# bristol_longshot.net
KiCad netlist of a schematic drawn in EAGLE
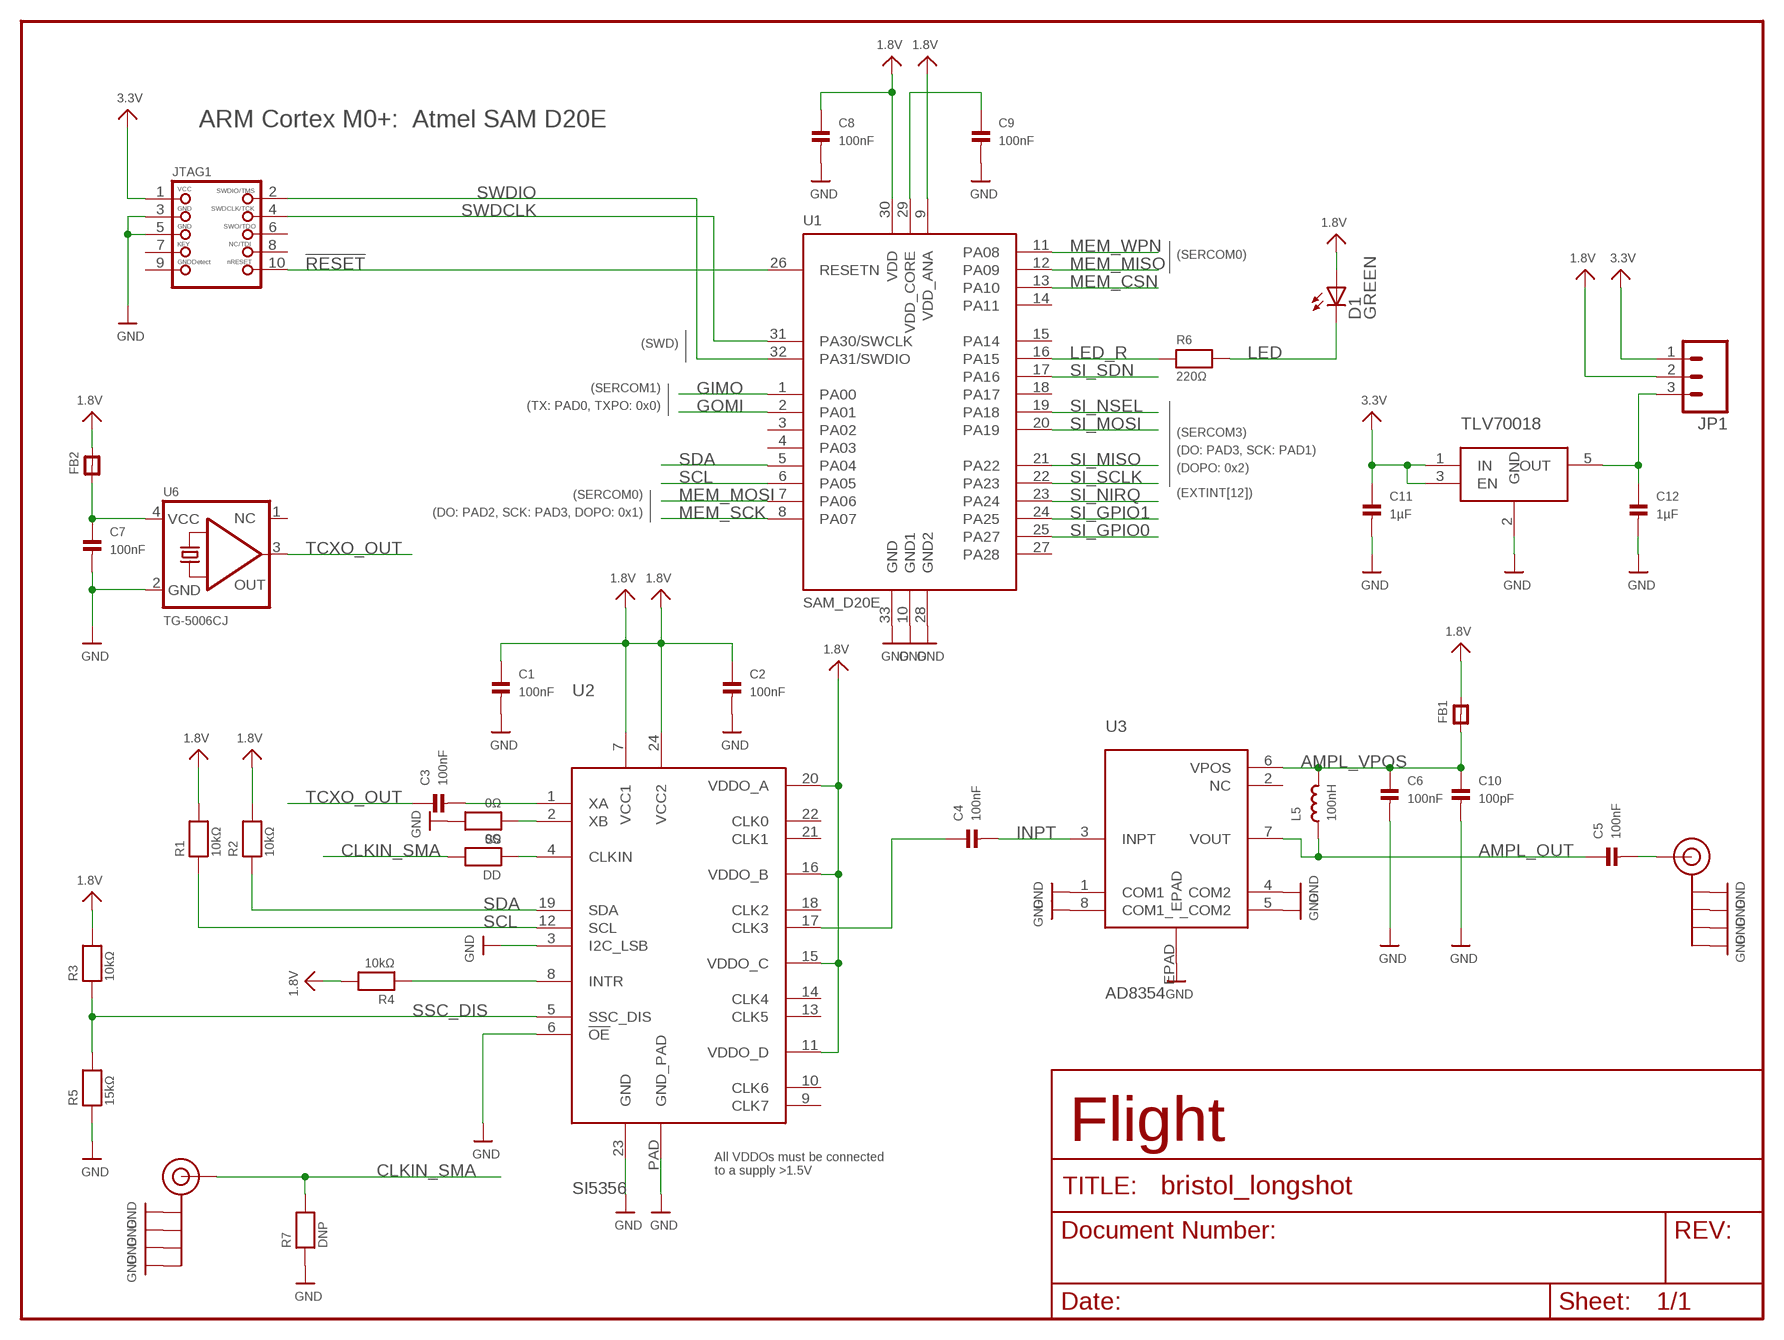
[diagram p0: schematic, sheet 1]

(export (version "E")
  (design (tool "Eeschema 10.0.6"))
  (components
    (comp (ref "C1")
      (value "100nF")
      (footprint "eagle-import:_0402")
      (libsource (lib "eagle-import") (part "CAP_CERAMIC_0402"))
    )
    (comp (ref "C2")
      (value "100nF")
      (footprint "eagle-import:_0402")
      (libsource (lib "eagle-import") (part "CAP_CERAMIC_0402"))
    )
    (comp (ref "C3")
      (value "100nF")
      (footprint "eagle-import:_0402")
      (libsource (lib "eagle-import") (part "CAP_CERAMIC_0402"))
    )
    (comp (ref "C4")
      (value "100nF")
      (footprint "eagle-import:_0402")
      (libsource (lib "eagle-import") (part "CAP_CERAMIC_0402"))
    )
    (comp (ref "C5")
      (value "100nF")
      (footprint "eagle-import:_0402")
      (libsource (lib "eagle-import") (part "CAP_CERAMIC_0402"))
    )
    (comp (ref "C6")
      (value "100nF")
      (footprint "eagle-import:_0402")
      (libsource (lib "eagle-import") (part "CAP_CERAMIC_0402"))
    )
    (comp (ref "C7")
      (value "100nF")
      (footprint "eagle-import:_0402")
      (libsource (lib "eagle-import") (part "CAP_CERAMIC_0402"))
    )
    (comp (ref "C8")
      (value "100nF")
      (footprint "eagle-import:_0402")
      (libsource (lib "eagle-import") (part "CAP_CERAMIC_0402"))
    )
    (comp (ref "C9")
      (value "100nF")
      (footprint "eagle-import:_0402")
      (libsource (lib "eagle-import") (part "CAP_CERAMIC_0402"))
    )
    (comp (ref "C10")
      (value "100pF")
      (footprint "eagle-import:_0402")
      (libsource (lib "eagle-import") (part "CAP_CERAMIC_0402"))
    )
    (comp (ref "C11")
      (value "1µF")
      (footprint "eagle-import:_0402")
      (libsource (lib "eagle-import") (part "CAP_CERAMIC_0402"))
    )
    (comp (ref "C12")
      (value "1µF")
      (footprint "eagle-import:_0402")
      (libsource (lib "eagle-import") (part "CAP_CERAMIC_0402"))
    )
    (comp (ref "D1")
      (value "GREEN")
      (footprint "eagle-import:CHIPLED_0603")
      (libsource (lib "eagle-import") (part "LEDCHIPLED_0603"))
    )
    (comp (ref "DD")
      (value "0Ω")
      (footprint "eagle-import:_0402")
      (libsource (lib "eagle-import") (part "RESISTOR_0402"))
    )
    (comp (ref "FB1")
      (value "FERRITE_0402")
      (footprint "eagle-import:_0402")
      (libsource (lib "eagle-import") (part "FERRITE_0402"))
    )
    (comp (ref "FB2")
      (value "FERRITE_0402")
      (footprint "eagle-import:_0402")
      (libsource (lib "eagle-import") (part "FERRITE_0402"))
    )
    (comp (ref "J$1")
      (value "SMA_EDGE")
      (footprint "eagle-import:SMA-EDGE")
      (libsource (lib "eagle-import") (part "SMA_EDGE"))
    )
    (comp (ref "J$2")
      (value "SMA_EDGE")
      (footprint "eagle-import:SMA-EDGE")
      (libsource (lib "eagle-import") (part "SMA_EDGE"))
    )
    (comp (ref "JP1")
      (value "M03LOCK")
      (footprint "eagle-import:1X03_LOCK")
      (libsource (lib "eagle-import") (part "M03LOCK"))
    )
    (comp (ref "JTAG1")
      (value "JTAG-CORTEXM3SMT")
      (footprint "eagle-import:2X05_1.27MM_SMT")
      (libsource (lib "eagle-import") (part "JTAG-CORTEXM3SMT"))
    )
    (comp (ref "L5")
      (value "100nH")
      (footprint "eagle-import:_0402")
      (libsource (lib "eagle-import") (part "INDUCTOR_0402"))
    )
    (comp (ref "R1")
      (value "10kΩ")
      (footprint "eagle-import:_0402")
      (libsource (lib "eagle-import") (part "RESISTOR_0402"))
    )
    (comp (ref "R2")
      (value "10kΩ")
      (footprint "eagle-import:_0402")
      (libsource (lib "eagle-import") (part "RESISTOR_0402"))
    )
    (comp (ref "R3")
      (value "10kΩ")
      (footprint "eagle-import:_0402")
      (libsource (lib "eagle-import") (part "RESISTOR_0402"))
    )
    (comp (ref "R4")
      (value "10kΩ")
      (footprint "eagle-import:_0402")
      (libsource (lib "eagle-import") (part "RESISTOR_0402"))
    )
    (comp (ref "R5")
      (value "15kΩ")
      (footprint "eagle-import:_0402")
      (libsource (lib "eagle-import") (part "RESISTOR_0402"))
    )
    (comp (ref "R6")
      (value "220Ω")
      (footprint "eagle-import:_0402")
      (libsource (lib "eagle-import") (part "RESISTOR_0402"))
    )
    (comp (ref "R7")
      (value "DNP")
      (footprint "eagle-import:_0402")
      (libsource (lib "eagle-import") (part "RESISTOR_0402"))
    )
    (comp (ref "SS")
      (value "0Ω")
      (footprint "eagle-import:_0402")
      (libsource (lib "eagle-import") (part "RESISTOR_0402"))
    )
    (comp (ref "U1")
      (value "SAM_D20E")
      (footprint "eagle-import:QFN32_5MM")
      (libsource (lib "eagle-import") (part "SAM_D20E"))
    )
    (comp (ref "U2")
      (value "SI5356")
      (footprint "eagle-import:QFN24_4MM")
      (libsource (lib "eagle-import") (part "SI5356"))
    )
    (comp (ref "U3")
      (value "AD8354")
      (footprint "eagle-import:LFCSP_VD_8")
      (libsource (lib "eagle-import") (part "AD8354"))
    )
    (comp (ref "U4")
      (value "TLV70018DCK")
      (footprint "eagle-import:SC70-5L")
      (libsource (lib "eagle-import") (part "TLV700DCK"))
    )
    (comp (ref "U6")
      (value "TG-5006CJ")
      (footprint "eagle-import:TC-5006CJ")
      (libsource (lib "eagle-import") (part "TG-5006CJ"))
    )
  )
  (nets
    (net (code "1") (name "/AMPL_OUT") (class "Default")
      (node (ref "C5") (pin "1") (pinfunction "P$1_1") (pintype "passive"))
      (node (ref "L5") (pin "1") (pinfunction "1_1") (pintype "passive"))
      (node (ref "U3") (pin "7") (pinfunction "VOUT_7") (pintype "bidirectional"))
    )
    (net (code "2") (name "/AMPL_VPOS") (class "Default")
      (node (ref "C10") (pin "1") (pinfunction "P$1_1") (pintype "passive"))
      (node (ref "C6") (pin "1") (pinfunction "P$1_1") (pintype "passive"))
      (node (ref "FB1") (pin "1") (pinfunction "P$1_1") (pintype "passive"))
      (node (ref "L5") (pin "2") (pinfunction "2_2") (pintype "passive"))
      (node (ref "U3") (pin "6") (pinfunction "VPOS_6") (pintype "bidirectional"))
    )
    (net (code "3") (name "/CLKIN_SMA") (class "Default")
      (node (ref "DD") (pin "2") (pinfunction "2_2") (pintype "passive"))
      (node (ref "J$1") (pin "SIG") (pinfunction "SIGNAL_SIG") (pintype "bidirectional"))
      (node (ref "R7") (pin "2") (pinfunction "2_2") (pintype "passive"))
    )
    (net (code "4") (name "/GIMO") (class "Default")
      (node (ref "U1") (pin "1") (pinfunction "PA00_1") (pintype "bidirectional"))
    )
    (net (code "5") (name "/GOMI") (class "Default")
      (node (ref "U1") (pin "2") (pinfunction "PA01_2") (pintype "bidirectional"))
    )
    (net (code "6") (name "/INPT") (class "Default")
      (node (ref "C4") (pin "2") (pinfunction "P$2_2") (pintype "passive"))
      (node (ref "U3") (pin "3") (pinfunction "INPT_3") (pintype "bidirectional"))
    )
    (net (code "7") (name "/LED") (class "Default")
      (node (ref "D1") (pin "C") (pinfunction "C_C") (pintype "passive"))
      (node (ref "R6") (pin "2") (pinfunction "2_2") (pintype "passive"))
    )
    (net (code "8") (name "/LED_R") (class "Default")
      (node (ref "R6") (pin "1") (pinfunction "1_1") (pintype "passive"))
      (node (ref "U1") (pin "16") (pinfunction "PA15_16") (pintype "bidirectional"))
    )
    (net (code "9") (name "/MEM_CSN") (class "Default")
      (node (ref "U1") (pin "13") (pinfunction "PA10_13") (pintype "bidirectional"))
    )
    (net (code "10") (name "/MEM_MISO") (class "Default")
      (node (ref "U1") (pin "12") (pinfunction "PA09_12") (pintype "bidirectional"))
    )
    (net (code "11") (name "/MEM_MOSI") (class "Default")
      (node (ref "U1") (pin "7") (pinfunction "PA06_7") (pintype "bidirectional"))
    )
    (net (code "12") (name "/MEM_SCK") (class "Default")
      (node (ref "U1") (pin "8") (pinfunction "PA07_8") (pintype "bidirectional"))
    )
    (net (code "13") (name "/MEM_WPN") (class "Default")
      (node (ref "U1") (pin "11") (pinfunction "PA08_11") (pintype "bidirectional"))
    )
    (net (code "14") (name "/SCL") (class "Default")
      (node (ref "R1") (pin "1") (pinfunction "1_1") (pintype "passive"))
      (node (ref "U1") (pin "6") (pinfunction "PA05_6") (pintype "bidirectional"))
      (node (ref "U2") (pin "12") (pinfunction "SCL_12") (pintype "bidirectional"))
    )
    (net (code "15") (name "/SDA") (class "Default")
      (node (ref "R2") (pin "1") (pinfunction "1_1") (pintype "passive"))
      (node (ref "U1") (pin "5") (pinfunction "PA04_5") (pintype "bidirectional"))
      (node (ref "U2") (pin "19") (pinfunction "SDA_19") (pintype "bidirectional"))
    )
    (net (code "16") (name "/SI_GPIO0") (class "Default")
      (node (ref "U1") (pin "25") (pinfunction "PA27_25") (pintype "bidirectional"))
    )
    (net (code "17") (name "/SI_GPIO1") (class "Default")
      (node (ref "U1") (pin "24") (pinfunction "PA25_24") (pintype "bidirectional"))
    )
    (net (code "18") (name "/SI_MISO") (class "Default")
      (node (ref "U1") (pin "21") (pinfunction "PA22_21") (pintype "bidirectional"))
    )
    (net (code "19") (name "/SI_MOSI") (class "Default")
      (node (ref "U1") (pin "20") (pinfunction "PA19_20") (pintype "bidirectional"))
    )
    (net (code "20") (name "/SI_NIRQ") (class "Default")
      (node (ref "U1") (pin "23") (pinfunction "PA24_23") (pintype "bidirectional"))
    )
    (net (code "21") (name "/SI_NSEL") (class "Default")
      (node (ref "U1") (pin "19") (pinfunction "PA18_19") (pintype "bidirectional"))
    )
    (net (code "22") (name "/SI_SCLK") (class "Default")
      (node (ref "U1") (pin "22") (pinfunction "PA23_22") (pintype "bidirectional"))
    )
    (net (code "23") (name "/SI_SDN") (class "Default")
      (node (ref "U1") (pin "17") (pinfunction "PA16_17") (pintype "bidirectional"))
    )
    (net (code "24") (name "/SSC_DIS") (class "Default")
      (node (ref "R3") (pin "1") (pinfunction "1_1") (pintype "passive"))
      (node (ref "R5") (pin "2") (pinfunction "2_2") (pintype "passive"))
      (node (ref "U2") (pin "5") (pinfunction "SSC_DIS_5") (pintype "bidirectional"))
    )
    (net (code "25") (name "/SWDCLK") (class "Default")
      (node (ref "JTAG1") (pin "4") (pinfunction "4_4") (pintype "passive"))
      (node (ref "U1") (pin "31") (pinfunction "PA30/SWCLK_31") (pintype "bidirectional"))
    )
    (net (code "26") (name "/SWDIO") (class "Default")
      (node (ref "JTAG1") (pin "2") (pinfunction "2_2") (pintype "passive"))
      (node (ref "U1") (pin "32") (pinfunction "PA31/SWDIO_32") (pintype "bidirectional"))
    )
    (net (code "27") (name "/TCXO_OUT") (class "Default")
      (node (ref "C3") (pin "1") (pinfunction "P$1_1") (pintype "passive"))
      (node (ref "U6") (pin "3") (pinfunction "OUT_3") (pintype "output"))
    )
    (net (code "28") (name "/~{RESET}") (class "Default")
      (node (ref "JTAG1") (pin "10") (pinfunction "10_10") (pintype "passive"))
      (node (ref "U1") (pin "26") (pinfunction "RESETN_26") (pintype "input"))
    )
    (net (code "29") (name "1.8V") (class "Default")
      (node (ref "C1") (pin "1") (pinfunction "P$1_1") (pintype "passive"))
      (node (ref "C2") (pin "1") (pinfunction "P$1_1") (pintype "passive"))
      (node (ref "C8") (pin "1") (pinfunction "P$1_1") (pintype "passive"))
      (node (ref "D1") (pin "A") (pinfunction "A_A") (pintype "passive"))
      (node (ref "FB1") (pin "2") (pinfunction "P$2_2") (pintype "passive"))
      (node (ref "FB2") (pin "2") (pinfunction "P$2_2") (pintype "passive"))
      (node (ref "JP1") (pin "2") (pinfunction "2_2") (pintype "passive"))
      (node (ref "R1") (pin "2") (pinfunction "2_2") (pintype "passive"))
      (node (ref "R2") (pin "2") (pinfunction "2_2") (pintype "passive"))
      (node (ref "R3") (pin "2") (pinfunction "2_2") (pintype "passive"))
      (node (ref "R4") (pin "2") (pinfunction "2_2") (pintype "passive"))
      (node (ref "U1") (pin "30") (pinfunction "VDD_30") (pintype "power_in"))
      (node (ref "U1") (pin "9") (pinfunction "VDD_ANA_9") (pintype "power_in"))
      (node (ref "U2") (pin "11") (pinfunction "VDDO_D_11") (pintype "bidirectional"))
      (node (ref "U2") (pin "15") (pinfunction "VDDO_C_15") (pintype "bidirectional"))
      (node (ref "U2") (pin "16") (pinfunction "VDDO_B_16") (pintype "bidirectional"))
      (node (ref "U2") (pin "20") (pinfunction "VDDO_A_20") (pintype "bidirectional"))
      (node (ref "U2") (pin "24") (pinfunction "VCC2_24") (pintype "bidirectional"))
      (node (ref "U2") (pin "7") (pinfunction "VCC1_7") (pintype "bidirectional"))
    )
    (net (code "30") (name "3.3V") (class "Default")
      (node (ref "C11") (pin "1") (pinfunction "P$1_1") (pintype "passive"))
      (node (ref "JP1") (pin "1") (pinfunction "1_1") (pintype "passive"))
      (node (ref "JTAG1") (pin "1") (pinfunction "1_1") (pintype "passive"))
      (node (ref "U4") (pin "1") (pinfunction "IN_1") (pintype "bidirectional"))
      (node (ref "U4") (pin "3") (pinfunction "EN_3") (pintype "bidirectional"))
    )
    (net (code "31") (name "GND") (class "Default")
      (node (ref "C1") (pin "2") (pinfunction "P$2_2") (pintype "passive"))
      (node (ref "C10") (pin "2") (pinfunction "P$2_2") (pintype "passive"))
      (node (ref "C11") (pin "2") (pinfunction "P$2_2") (pintype "passive"))
      (node (ref "C12") (pin "2") (pinfunction "P$2_2") (pintype "passive"))
      (node (ref "C2") (pin "2") (pinfunction "P$2_2") (pintype "passive"))
      (node (ref "C6") (pin "2") (pinfunction "P$2_2") (pintype "passive"))
      (node (ref "C7") (pin "2") (pinfunction "P$2_2") (pintype "passive"))
      (node (ref "C8") (pin "2") (pinfunction "P$2_2") (pintype "passive"))
      (node (ref "C9") (pin "2") (pinfunction "P$2_2") (pintype "passive"))
      (node (ref "J$1") (pin "GND@0") (pinfunction "GND_GND@0") (pintype "bidirectional"))
      (node (ref "J$1") (pin "GND@1") (pinfunction "GND_GND@1") (pintype "bidirectional"))
      (node (ref "J$1") (pin "GND@2") (pinfunction "GND_GND@2") (pintype "bidirectional"))
      (node (ref "J$1") (pin "GND@3") (pinfunction "GND_GND@3") (pintype "bidirectional"))
      (node (ref "J$2") (pin "GND@0") (pinfunction "GND_GND@0") (pintype "bidirectional"))
      (node (ref "J$2") (pin "GND@1") (pinfunction "GND_GND@1") (pintype "bidirectional"))
      (node (ref "J$2") (pin "GND@2") (pinfunction "GND_GND@2") (pintype "bidirectional"))
      (node (ref "J$2") (pin "GND@3") (pinfunction "GND_GND@3") (pintype "bidirectional"))
      (node (ref "JTAG1") (pin "3") (pinfunction "3_3") (pintype "passive"))
      (node (ref "JTAG1") (pin "5") (pinfunction "5_5") (pintype "passive"))
      (node (ref "R5") (pin "1") (pinfunction "1_1") (pintype "passive"))
      (node (ref "R7") (pin "1") (pinfunction "1_1") (pintype "passive"))
      (node (ref "SS") (pin "2") (pinfunction "2_2") (pintype "passive"))
      (node (ref "U1") (pin "10") (pinfunction "GND1_10") (pintype "power_in"))
      (node (ref "U1") (pin "28") (pinfunction "GND2_28") (pintype "power_in"))
      (node (ref "U1") (pin "33") (pinfunction "GND_33") (pintype "power_in"))
      (node (ref "U2") (pin "23") (pinfunction "GND_23") (pintype "bidirectional"))
      (node (ref "U2") (pin "3") (pinfunction "I2C_LSB_3") (pintype "bidirectional"))
      (node (ref "U2") (pin "6") (pinfunction "~{OE}_6") (pintype "bidirectional"))
      (node (ref "U2") (pin "PAD") (pinfunction "GND_PAD_PAD") (pintype "bidirectional"))
      (node (ref "U3") (pin "1") (pinfunction "COM1_1") (pintype "bidirectional"))
      (node (ref "U3") (pin "4") (pinfunction "COM2_4") (pintype "bidirectional"))
      (node (ref "U3") (pin "5") (pinfunction "_COM2_5") (pintype "bidirectional"))
      (node (ref "U3") (pin "8") (pinfunction "COM1__8") (pintype "bidirectional"))
      (node (ref "U3") (pin "EPAD") (pinfunction "EPAD_EPAD") (pintype "bidirectional"))
      (node (ref "U4") (pin "2") (pinfunction "GND_2") (pintype "bidirectional"))
      (node (ref "U6") (pin "2") (pinfunction "GND_2") (pintype "power_in"))
    )
    (net (code "32") (name "Net-(C3-P$2)") (class "Default")
      (node (ref "C3") (pin "2") (pinfunction "P$2_2") (pintype "passive"))
      (node (ref "U2") (pin "1") (pinfunction "XA_1") (pintype "bidirectional"))
    )
    (net (code "33") (name "Net-(C4-P$1)") (class "Default")
      (node (ref "C4") (pin "1") (pinfunction "P$1_1") (pintype "passive"))
      (node (ref "U2") (pin "17") (pinfunction "CLK3_17") (pintype "bidirectional"))
    )
    (net (code "34") (name "Net-(C5-P$2)") (class "Default")
      (node (ref "C5") (pin "2") (pinfunction "P$2_2") (pintype "passive"))
      (node (ref "J$2") (pin "SIG") (pinfunction "SIGNAL_SIG") (pintype "bidirectional"))
    )
    (net (code "35") (name "Net-(C7-P$1)") (class "Default")
      (node (ref "C7") (pin "1") (pinfunction "P$1_1") (pintype "passive"))
      (node (ref "FB2") (pin "1") (pinfunction "P$1_1") (pintype "passive"))
      (node (ref "U6") (pin "4") (pinfunction "VCC_4") (pintype "power_in"))
    )
    (net (code "36") (name "Net-(C9-P$1)") (class "Default")
      (node (ref "C9") (pin "1") (pinfunction "P$1_1") (pintype "passive"))
      (node (ref "U1") (pin "29") (pinfunction "VDD_CORE_29") (pintype "power_in"))
    )
    (net (code "37") (name "Net-(C12-P$1)") (class "Default")
      (node (ref "C12") (pin "1") (pinfunction "P$1_1") (pintype "passive"))
      (node (ref "JP1") (pin "3") (pinfunction "3_3") (pintype "passive"))
      (node (ref "U4") (pin "5") (pinfunction "OUT_5") (pintype "bidirectional"))
    )
    (net (code "38") (name "Net-(U2-CLKIN)") (class "Default")
      (node (ref "DD") (pin "1") (pinfunction "1_1") (pintype "passive"))
      (node (ref "U2") (pin "4") (pinfunction "CLKIN_4") (pintype "bidirectional"))
    )
    (net (code "39") (name "Net-(U2-INTR)") (class "Default")
      (node (ref "R4") (pin "1") (pinfunction "1_1") (pintype "passive"))
      (node (ref "U2") (pin "8") (pinfunction "INTR_8") (pintype "bidirectional"))
    )
    (net (code "40") (name "Net-(U2-XB)") (class "Default")
      (node (ref "SS") (pin "1") (pinfunction "1_1") (pintype "passive"))
      (node (ref "U2") (pin "2") (pinfunction "XB_2") (pintype "bidirectional"))
    )
    (net (code "41") (name "unconnected-(JTAG1-Pad6)") (class "Default")
      (node (ref "JTAG1") (pin "6") (pinfunction "6_6") (pintype "passive"))
    )
    (net (code "42") (name "unconnected-(JTAG1-Pad7)") (class "Default")
      (node (ref "JTAG1") (pin "7") (pinfunction "7_7") (pintype "passive"))
    )
    (net (code "43") (name "unconnected-(JTAG1-Pad8)") (class "Default")
      (node (ref "JTAG1") (pin "8") (pinfunction "8_8") (pintype "passive"))
    )
    (net (code "44") (name "unconnected-(JTAG1-Pad9)") (class "Default")
      (node (ref "JTAG1") (pin "9") (pinfunction "9_9") (pintype "passive"))
    )
    (net (code "45") (name "unconnected-(U1-PA02-Pad3)") (class "Default")
      (node (ref "U1") (pin "3") (pinfunction "PA02_3") (pintype "bidirectional"))
    )
    (net (code "46") (name "unconnected-(U1-PA03-Pad4)") (class "Default")
      (node (ref "U1") (pin "4") (pinfunction "PA03_4") (pintype "bidirectional"))
    )
    (net (code "47") (name "unconnected-(U1-PA11-Pad14)") (class "Default")
      (node (ref "U1") (pin "14") (pinfunction "PA11_14") (pintype "bidirectional"))
    )
    (net (code "48") (name "unconnected-(U1-PA14-Pad15)") (class "Default")
      (node (ref "U1") (pin "15") (pinfunction "PA14_15") (pintype "bidirectional"))
    )
    (net (code "49") (name "unconnected-(U1-PA17-Pad18)") (class "Default")
      (node (ref "U1") (pin "18") (pinfunction "PA17_18") (pintype "bidirectional"))
    )
    (net (code "50") (name "unconnected-(U1-PA28-Pad27)") (class "Default")
      (node (ref "U1") (pin "27") (pinfunction "PA28_27") (pintype "bidirectional"))
    )
    (net (code "51") (name "unconnected-(U2-CLK0-Pad22)") (class "Default")
      (node (ref "U2") (pin "22") (pinfunction "CLK0_22") (pintype "bidirectional"))
    )
    (net (code "52") (name "unconnected-(U2-CLK1-Pad21)") (class "Default")
      (node (ref "U2") (pin "21") (pinfunction "CLK1_21") (pintype "bidirectional"))
    )
    (net (code "53") (name "unconnected-(U2-CLK2-Pad18)") (class "Default")
      (node (ref "U2") (pin "18") (pinfunction "CLK2_18") (pintype "bidirectional"))
    )
    (net (code "54") (name "unconnected-(U2-CLK4-Pad14)") (class "Default")
      (node (ref "U2") (pin "14") (pinfunction "CLK4_14") (pintype "bidirectional"))
    )
    (net (code "55") (name "unconnected-(U2-CLK5-Pad13)") (class "Default")
      (node (ref "U2") (pin "13") (pinfunction "CLK5_13") (pintype "bidirectional"))
    )
    (net (code "56") (name "unconnected-(U2-CLK6-Pad10)") (class "Default")
      (node (ref "U2") (pin "10") (pinfunction "CLK6_10") (pintype "bidirectional"))
    )
    (net (code "57") (name "unconnected-(U2-CLK7-Pad9)") (class "Default")
      (node (ref "U2") (pin "9") (pinfunction "CLK7_9") (pintype "bidirectional"))
    )
    (net (code "58") (name "unconnected-(U3-NC-Pad2)") (class "Default")
      (node (ref "U3") (pin "2") (pinfunction "NC_2") (pintype "bidirectional"))
    )
    (net (code "59") (name "unconnected-(U6-NC-Pad1)") (class "Default")
      (node (ref "U6") (pin "1") (pinfunction "NC_1") (pintype "no_connect"))
    )
  )
)
